# HarvestRing.net
KiCad netlist of a schematic drawn in EAGLE
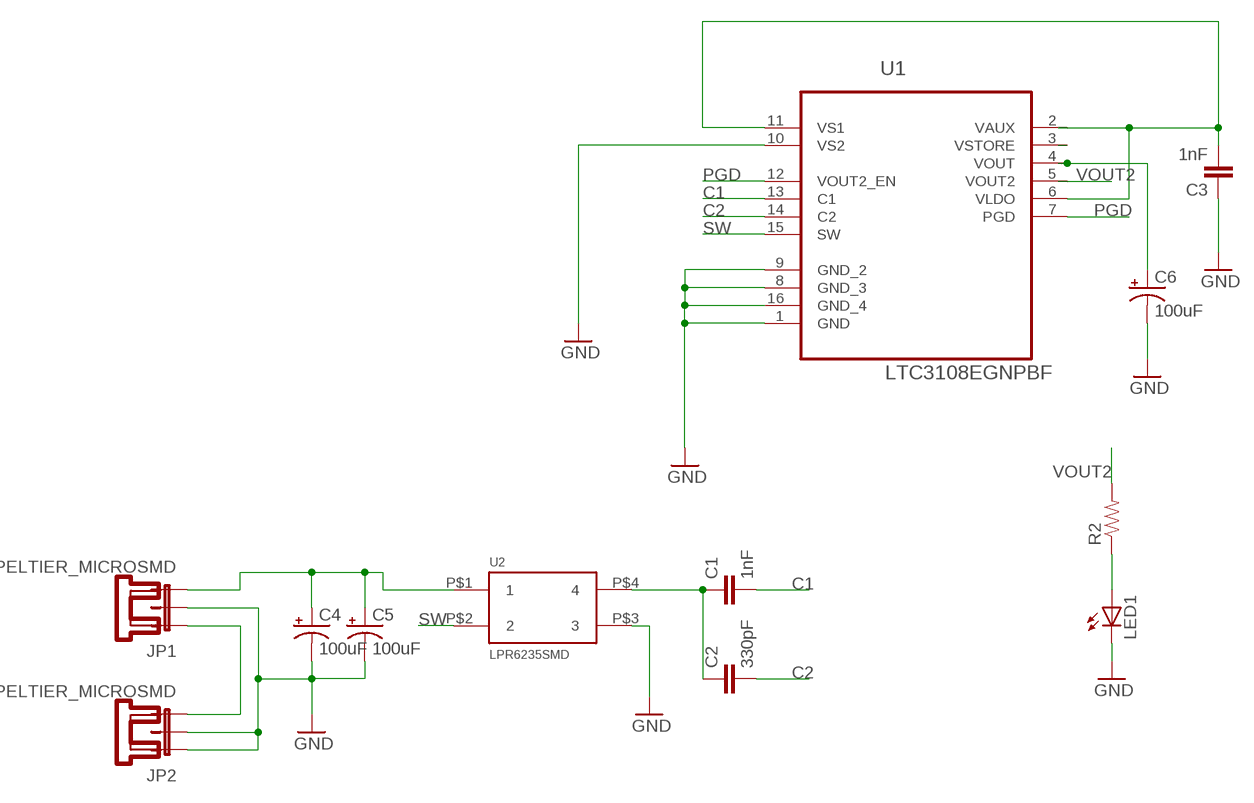
[diagram p0: schematic, sheet 1]

(export (version "E")
  (design (tool "Eeschema 10.0.6"))
  (components
    (comp (ref "C1")
      (value "1nF")
      (footprint "eagle-import:0603-CAP")
      (libsource (lib "eagle-import") (part "1NF/1000PF-50V-10%(0603)"))
    )
    (comp (ref "C2")
      (value "330pF")
      (footprint "eagle-import:0603-CAP")
      (libsource (lib "eagle-import") (part "22PF-50V-5%(0603)"))
    )
    (comp (ref "C3")
      (value "1nF")
      (footprint "eagle-import:0603-CAP")
      (libsource (lib "eagle-import") (part "1NF/1000PF-50V-10%(0603)"))
    )
    (comp (ref "C4")
      (value "100uF")
      (footprint "eagle-import:EIA3216")
      (libsource (lib "eagle-import") (part "10UF-TANT"))
    )
    (comp (ref "C5")
      (value "100uF")
      (footprint "eagle-import:EIA3216")
      (libsource (lib "eagle-import") (part "10UF-TANT"))
    )
    (comp (ref "C6")
      (value "100uF")
      (footprint "eagle-import:EIA3216")
      (libsource (lib "eagle-import") (part "10UF-TANT"))
    )
    (comp (ref "JP1")
      (value "PELTIER_MICROSMD")
      (footprint "eagle-import:HV56")
      (libsource (lib "eagle-import") (part "PELTIER_MICROSMD"))
    )
    (comp (ref "JP2")
      (value "PELTIER_MICROSMD")
      (footprint "eagle-import:HV56")
      (libsource (lib "eagle-import") (part "PELTIER_MICROSMD"))
    )
    (comp (ref "LED1")
      (value "LED1206")
      (footprint "eagle-import:LED-1206")
      (libsource (lib "eagle-import") (part "LED1206"))
    )
    (comp (ref "R2")
      (value "22K")
      (footprint "eagle-import:0603-RES")
      (libsource (lib "eagle-import") (part "22KOHM1/10W1%(0603)"))
    )
    (comp (ref "U1")
      (value "LTC3108EGNPBF")
      (footprint "eagle-import:SOP63P600X175-16N")
      (fields (field (name "MPN") "LTC3108EGN#PBF"))
      (libsource (lib "eagle-import") (part "LTC3108EGNPBF"))
    )
    (comp (ref "U2")
      (value "LPR6235SMD")
      (footprint "eagle-import:LPR6235")
      (libsource (lib "eagle-import") (part "LPR6235SMD"))
    )
  )
  (nets
    (net (code "1") (name "/C1") (class "Default")
      (node (ref "C1") (pin "2") (pinfunction "2_2") (pintype "passive"))
      (node (ref "U1") (pin "13") (pinfunction "C1_13") (pintype "input"))
    )
    (net (code "2") (name "/C2") (class "Default")
      (node (ref "C2") (pin "2") (pinfunction "2_2") (pintype "passive"))
      (node (ref "U1") (pin "14") (pinfunction "C2_14") (pintype "input"))
    )
    (net (code "3") (name "/PGD") (class "Default")
      (node (ref "U1") (pin "12") (pinfunction "VOUT2_EN_12") (pintype "input"))
      (node (ref "U1") (pin "7") (pinfunction "PGD_7") (pintype "output"))
    )
    (net (code "4") (name "/SW") (class "Default")
      (node (ref "U1") (pin "15") (pinfunction "SW_15") (pintype "passive"))
      (node (ref "U2") (pin "P$2") (pinfunction "2_P$2") (pintype "bidirectional"))
    )
    (net (code "5") (name "/VOUT2") (class "Default")
      (node (ref "R2") (pin "2") (pinfunction "2_2") (pintype "passive"))
      (node (ref "U1") (pin "5") (pinfunction "VOUT2_5") (pintype "output"))
    )
    (net (code "6") (name "GND") (class "Default")
      (node (ref "C3") (pin "1") (pinfunction "1_1") (pintype "passive"))
      (node (ref "C4") (pin "C") (pinfunction "-_C") (pintype "passive"))
      (node (ref "C5") (pin "C") (pinfunction "-_C") (pintype "passive"))
      (node (ref "C6") (pin "C") (pinfunction "-_C") (pintype "passive"))
      (node (ref "JP1") (pin "2") (pinfunction "2_2") (pintype "passive"))
      (node (ref "JP2") (pin "1") (pinfunction "1_1") (pintype "output"))
      (node (ref "JP2") (pin "2") (pinfunction "2_2") (pintype "passive"))
      (node (ref "LED1") (pin "C") (pinfunction "C_C") (pintype "passive"))
      (node (ref "U1") (pin "1") (pinfunction "GND_1") (pintype "passive"))
      (node (ref "U1") (pin "10") (pinfunction "VS2_10") (pintype "input"))
      (node (ref "U1") (pin "16") (pinfunction "GND_4_16") (pintype "passive"))
      (node (ref "U1") (pin "8") (pinfunction "GND_3_8") (pintype "passive"))
      (node (ref "U1") (pin "9") (pinfunction "GND_2_9") (pintype "passive"))
      (node (ref "U2") (pin "P$3") (pinfunction "3_P$3") (pintype "bidirectional"))
    )
    (net (code "7") (name "Net-(C4-+)") (class "Default")
      (node (ref "C4") (pin "A") (pinfunction "+_A") (pintype "passive"))
      (node (ref "C5") (pin "A") (pinfunction "+_A") (pintype "passive"))
      (node (ref "JP1") (pin "3") (pinfunction "3_3") (pintype "output"))
      (node (ref "U2") (pin "P$1") (pinfunction "1_P$1") (pintype "bidirectional"))
    )
    (net (code "8") (name "Net-(C6-+)") (class "Default")
      (node (ref "C6") (pin "A") (pinfunction "+_A") (pintype "passive"))
      (node (ref "U1") (pin "4") (pinfunction "VOUT_4") (pintype "output"))
    )
    (net (code "9") (name "Net-(JP1-Pad1)") (class "Default")
      (node (ref "JP1") (pin "1") (pinfunction "1_1") (pintype "output"))
      (node (ref "JP2") (pin "3") (pinfunction "3_3") (pintype "output"))
    )
    (net (code "10") (name "Net-(LED1-PadA)") (class "Default")
      (node (ref "LED1") (pin "A") (pinfunction "A_A") (pintype "passive"))
      (node (ref "R2") (pin "1") (pinfunction "1_1") (pintype "passive"))
    )
    (net (code "11") (name "Net-(U1-VAUX)") (class "Default")
      (node (ref "C3") (pin "2") (pinfunction "2_2") (pintype "passive"))
      (node (ref "U1") (pin "11") (pinfunction "VS1_11") (pintype "input"))
      (node (ref "U1") (pin "2") (pinfunction "VAUX_2") (pintype "output"))
      (node (ref "U1") (pin "6") (pinfunction "VLDO_6") (pintype "output"))
    )
    (net (code "12") (name "Net-(U2-4)") (class "Default")
      (node (ref "C1") (pin "1") (pinfunction "1_1") (pintype "passive"))
      (node (ref "C2") (pin "1") (pinfunction "1_1") (pintype "passive"))
      (node (ref "U2") (pin "P$4") (pinfunction "4_P$4") (pintype "bidirectional"))
    )
    (net (code "13") (name "unconnected-(U1-VSTORE-Pad3)") (class "Default")
      (node (ref "U1") (pin "3") (pinfunction "VSTORE_3") (pintype "output"))
    )
  )
)
